# SCH_RejsaCAN_v2_5.net
KiCad netlist of a schematic drawn in EasyEDA
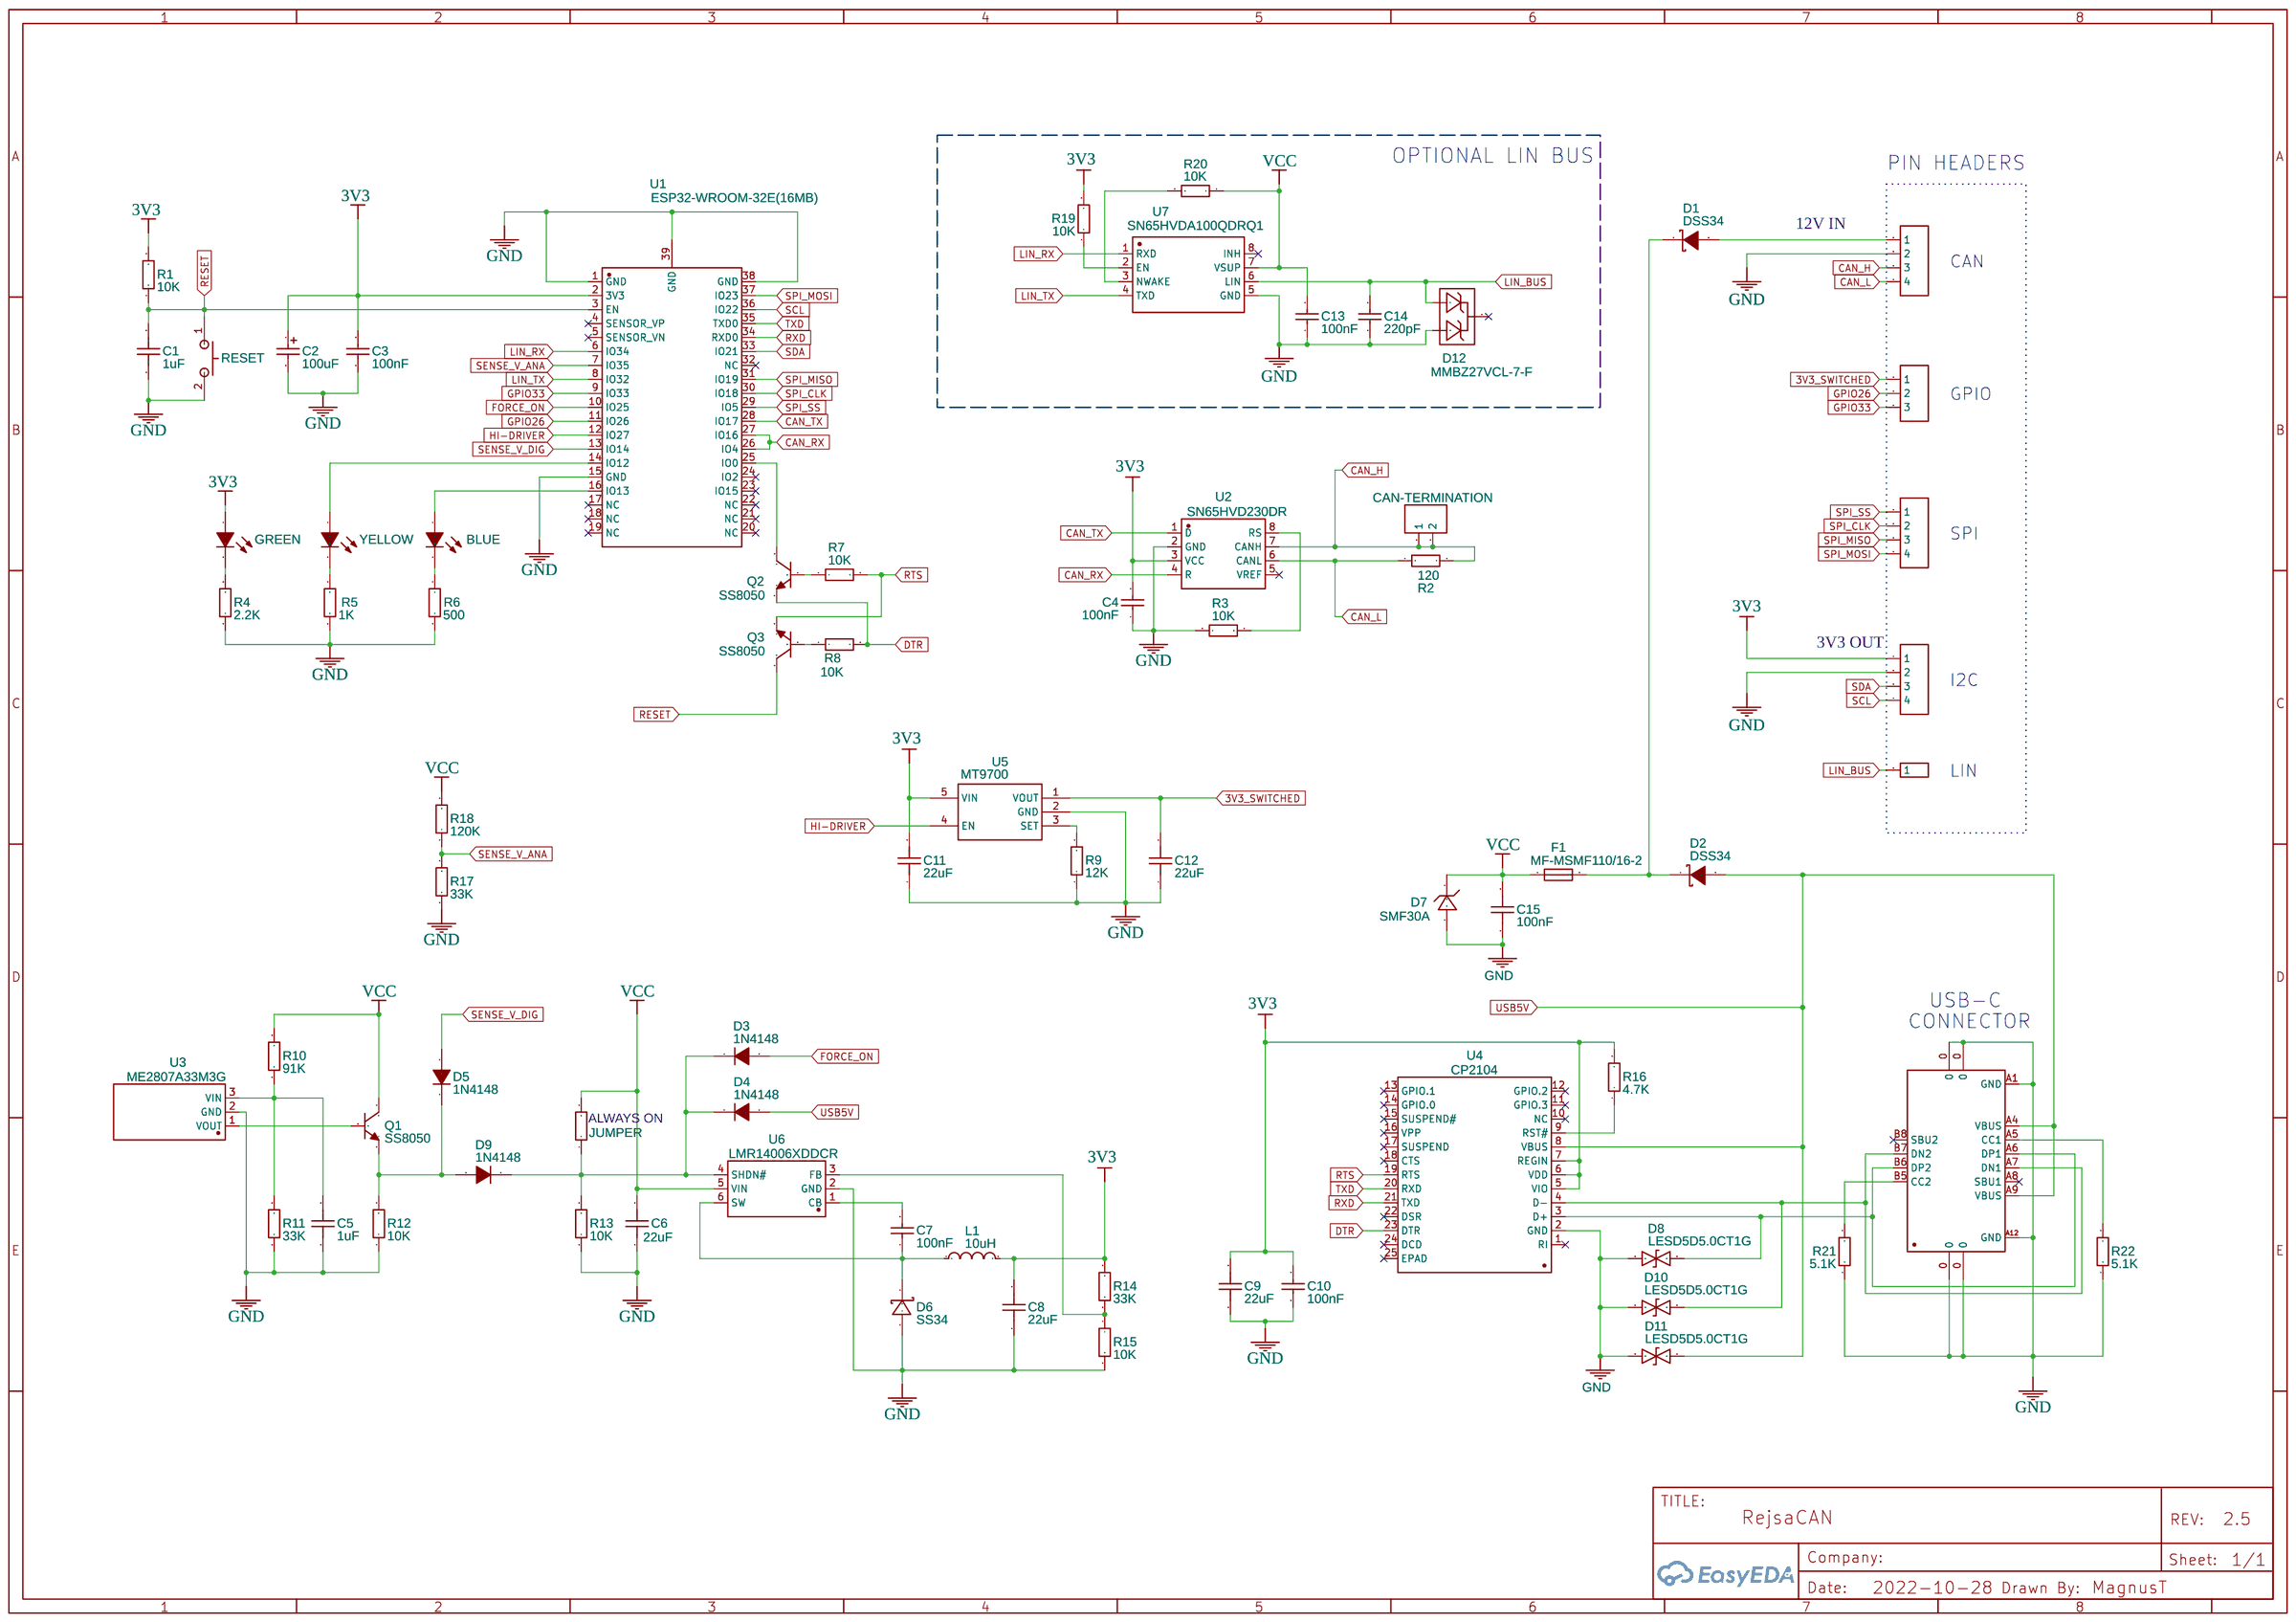
[diagram p0: schematic sheet]

(export (version "E")
  (design (tool "Eeschema 10.0.6"))
  (components
    (comp (ref "BLUE")
      (value "19-217/BHC-ZL1M2RY/3T")
      (fields (field (name "Manufacturer") "EVERLIGHT"))
      (libsource (lib "") (part "19-217/BHC-ZL1M2RY/3T"))
    )
    (comp (ref "C1")
      (value "1uF")
      (fields (field (name "Manufacturer Part") "CL05A105KA5NQNC") (field (name "Manufacturer") "SAMSUNG"))
      (libsource (lib "") (part "CL05A105KA5NQNC"))
    )
    (comp (ref "C2")
      (value "100uF")
      (fields (field (name "Manufacturer Part") "TAJB107K006RNJ") (field (name "Manufacturer") "AVX"))
      (libsource (lib "") (part "TAJB107K006RNJ"))
    )
    (comp (ref "C3")
      (value "100nF")
      (fields (field (name "Manufacturer Part") "CL05B104KO5NNNC") (field (name "Manufacturer") "SAMSUNG"))
      (libsource (lib "") (part "CL05B104KO5NNNC_1"))
    )
    (comp (ref "C4")
      (value "100nF")
      (fields (field (name "Manufacturer Part") "CL05B104KO5NNNC") (field (name "Manufacturer") "SAMSUNG"))
      (libsource (lib "") (part "CL05B104KO5NNNC"))
    )
    (comp (ref "C5")
      (value "1uF")
      (fields (field (name "Manufacturer Part") "CL05A105KA5NQNC") (field (name "Manufacturer") "SAMSUNG"))
      (libsource (lib "") (part "CL05A105KA5NQNC"))
    )
    (comp (ref "C6")
      (value "22uF")
      (fields
        (field (name "Manufacturer Part") "CL21A226MAYNNNE")
        (field (name "Manufacturer") "Samsung Electro-Mechanics")
      )
      (libsource (lib "") (part "CL21A226MAYNNNE"))
    )
    (comp (ref "C7")
      (value "100nF")
      (fields (field (name "Manufacturer Part") "CL05B104KO5NNNC") (field (name "Manufacturer") "SAMSUNG"))
      (libsource (lib "") (part "CL05B104KO5NNNC_1"))
    )
    (comp (ref "C8")
      (value "22uF")
      (fields (field (name "Manufacturer Part") "CL10A226MQ8NRNC") (field (name "Manufacturer") "SAMSUNG"))
      (libsource (lib "") (part "CL10A226MQ8NRNC"))
    )
    (comp (ref "C9")
      (value "22uF")
      (fields (field (name "Manufacturer Part") "CL10A226MQ8NRNC") (field (name "Manufacturer") "SAMSUNG"))
      (libsource (lib "") (part "CL10A226MQ8NRNC"))
    )
    (comp (ref "C10")
      (value "100nF")
      (fields (field (name "Manufacturer Part") "CL05B104KO5NNNC") (field (name "Manufacturer") "SAMSUNG"))
      (libsource (lib "") (part "CL05B104KO5NNNC_1"))
    )
    (comp (ref "C11")
      (value "22uF")
      (fields (field (name "Manufacturer Part") "CL10A226MQ8NRNC") (field (name "Manufacturer") "SAMSUNG"))
      (libsource (lib "") (part "CL10A226MQ8NRNC"))
    )
    (comp (ref "C12")
      (value "22uF")
      (fields (field (name "Manufacturer Part") "CL10A226MQ8NRNC") (field (name "Manufacturer") "SAMSUNG"))
      (libsource (lib "") (part "CL10A226MQ8NRNC"))
    )
    (comp (ref "C13")
      (value "100nF")
      (fields (field (name "Manufacturer Part") "CL05B104KO5NNNC") (field (name "Manufacturer") "SAMSUNG"))
      (libsource (lib "") (part "CL05B104KO5NNNC_1"))
    )
    (comp (ref "C14")
      (value "220pF")
      (fields (field (name "Manufacturer Part") "0402B221K500NT") (field (name "Manufacturer") "FH"))
      (libsource (lib "") (part "0402B221K500NT"))
    )
    (comp (ref "C15")
      (value "100nF")
      (fields
        (field (name "Manufacturer Part") "CL05B104KB54PNC")
        (field (name "Manufacturer") "Samsung Electro-Mechanics")
      )
      (libsource (lib "") (part "CL05B104KB54PNC"))
    )
    (comp (ref "CAN-TERMINATION") (value "HDR-M-2.54_1x2") (libsource (lib "") (part "HDR-M-2.54_1x2")))
    (comp (ref "D1")
      (value "DSS34")
      (fields (field (name "Manufacturer") "STARSEA"))
      (libsource (lib "") (part "DSS34"))
    )
    (comp (ref "D2")
      (value "DSS34")
      (fields (field (name "Manufacturer") "STARSEA"))
      (libsource (lib "") (part "DSS34"))
    )
    (comp (ref "D3")
      (value "1N4148")
      (fields (field (name "Manufacturer Part") "1N4148WS T4") (field (name "Manufacturer") "CJ"))
      (libsource (lib "") (part "1N4148WS T4"))
    )
    (comp (ref "D4")
      (value "1N4148")
      (fields (field (name "Manufacturer Part") "1N4148WS T4") (field (name "Manufacturer") "CJ"))
      (libsource (lib "") (part "1N4148WS T4"))
    )
    (comp (ref "D5")
      (value "1N4148")
      (fields (field (name "Manufacturer Part") "1N4148WS T4") (field (name "Manufacturer") "CJ"))
      (libsource (lib "") (part "1N4148WS T4_2"))
    )
    (comp (ref "D6")
      (value "SS34")
      (fields (field (name "Manufacturer") "MDD"))
      (libsource (lib "") (part "SS34_C8678"))
    )
    (comp (ref "D7")
      (value "SMF30A")
      (fields (field (name "Manufacturer") "DOWO"))
      (libsource (lib "") (part "SMF30A_C366558"))
    )
    (comp (ref "D8")
      (value "LESD5D5.0CT1G")
      (fields (field (name "Manufacturer") "Leshan Radio"))
      (libsource (lib "") (part "LESD5D5.0CT1G"))
    )
    (comp (ref "D9")
      (value "1N4148")
      (fields (field (name "Manufacturer Part") "1N4148WS T4") (field (name "Manufacturer") "CJ"))
      (libsource (lib "") (part "1N4148WS T4_1"))
    )
    (comp (ref "D10")
      (value "LESD5D5.0CT1G")
      (fields (field (name "Manufacturer") "Leshan Radio"))
      (libsource (lib "") (part "LESD5D5.0CT1G"))
    )
    (comp (ref "D11")
      (value "LESD5D5.0CT1G")
      (fields (field (name "Manufacturer") "Leshan Radio"))
      (libsource (lib "") (part "LESD5D5.0CT1G"))
    )
    (comp (ref "D12")
      (value "MMBZ27VCL-7-F")
      (fields (field (name "Manufacturer") "Diodes Incorporated"))
      (libsource (lib "") (part "MMBZ27VCL-7-F"))
    )
    (comp (ref "F1")
      (value "MF-MSMF110/16-2")
      (fields (field (name "Manufacturer") "BOURNS"))
      (libsource (lib "") (part "MF-MSMF110/16-2"))
    )
    (comp (ref "GREEN")
      (value "19-217/GHC-YR1S2/3T")
      (fields (field (name "Manufacturer") "EVERLIGHT"))
      (libsource (lib "") (part "19-217/GHC-YR1S2/3T"))
    )
    (comp (ref "J1") (value "HDR-M-2.54_1x4") (libsource (lib "") (part "HDR-M-2.54_1x4")))
    (comp (ref "J2") (value "HDR-M-2.54_1x4") (libsource (lib "") (part "HDR-M-2.54_1x4")))
    (comp (ref "J3") (value "HDR-M-2.54_1x4") (libsource (lib "") (part "HDR-M-2.54_1x4")))
    (comp (ref "J4") (value "HDR-M-2.54_1x3") (libsource (lib "") (part "HDR-M-2.54_1x3")))
    (comp (ref "J5") (value "HDR-M-2.54_1x1") (libsource (lib "") (part "HDR-M-2.54_1x1")))
    (comp (ref "JUMPER") (value "-") (libsource (lib "") (part "0402WGF3092TCE")))
    (comp (ref "L1")
      (value "10uH")
      (fields
        (field (name "Manufacturer Part") "SLP6028S100MTT")
        (field (name "Manufacturer") "Sunltech Tech")
      )
      (libsource (lib "") (part "SLP6028S100MTT"))
    )
    (comp (ref "Q1")
      (value "SS8050")
      (fields (field (name "Manufacturer") "CJ"))
      (libsource (lib "") (part "SS8050_C2150_1"))
    )
    (comp (ref "Q2")
      (value "SS8050")
      (fields (field (name "Manufacturer") "CJ"))
      (libsource (lib "") (part "SS8050_C2150_2"))
    )
    (comp (ref "Q3")
      (value "SS8050")
      (fields (field (name "Manufacturer") "CJ"))
      (libsource (lib "") (part "SS8050_C2150"))
    )
    (comp (ref "R1")
      (value "10K")
      (fields (field (name "Manufacturer Part") "0402WGF1002TCE") (field (name "Manufacturer") "UniOhm"))
      (libsource (lib "") (part "0402WGF1002TCE_1"))
    )
    (comp (ref "R2")
      (value "120")
      (fields (field (name "Manufacturer Part") "RTT061200FTP") (field (name "Manufacturer") "RALEC"))
      (libsource (lib "") (part "RTT061200FTP"))
    )
    (comp (ref "R3")
      (value "10K")
      (fields (field (name "Manufacturer Part") "0402WGF1002TCE") (field (name "Manufacturer") "UniOhm"))
      (libsource (lib "") (part "0402WGF1002TCE"))
    )
    (comp (ref "R4")
      (value "2.2K")
      (fields (field (name "Manufacturer Part") "0402WGF2201TCE") (field (name "Manufacturer") "UniOhm"))
      (libsource (lib "") (part "0402WGF2201TCE"))
    )
    (comp (ref "R5")
      (value "1K")
      (fields (field (name "Manufacturer Part") "0402WGF1001TCE") (field (name "Manufacturer") "UniOhm"))
      (libsource (lib "") (part "0402WGF1001TCE"))
    )
    (comp (ref "R6")
      (value "500")
      (fields (field (name "Manufacturer Part") "0402WGF4700TCE") (field (name "Manufacturer") "UniOhm"))
      (libsource (lib "") (part "0402WGF1001TCE"))
    )
    (comp (ref "R7")
      (value "10K")
      (fields (field (name "Manufacturer Part") "0402WGF1002TCE") (field (name "Manufacturer") "UniOhm"))
      (libsource (lib "") (part "0402WGF1002TCE"))
    )
    (comp (ref "R8")
      (value "10K")
      (fields (field (name "Manufacturer Part") "0402WGF1002TCE") (field (name "Manufacturer") "UniOhm"))
      (libsource (lib "") (part "0402WGF1002TCE"))
    )
    (comp (ref "R9")
      (value "12K")
      (fields (field (name "Manufacturer Part") "0402WGF1202TCE") (field (name "Manufacturer") "UniOhm"))
      (libsource (lib "") (part "0402WGF1202TCE"))
    )
    (comp (ref "R10")
      (value "91K")
      (fields (field (name "Manufacturer Part") "0402WGF9102TCE") (field (name "Manufacturer") "UniOhm"))
      (libsource (lib "") (part "0402WGF9102TCE"))
    )
    (comp (ref "R11")
      (value "33K")
      (fields (field (name "Manufacturer Part") "0402WGF3302TCE") (field (name "Manufacturer") "UniOhm"))
      (libsource (lib "") (part "0402WGF3302TCE"))
    )
    (comp (ref "R12")
      (value "10K")
      (fields (field (name "Manufacturer Part") "0402WGF1002TCE") (field (name "Manufacturer") "UniOhm"))
      (libsource (lib "") (part "0402WGF1002TCE_1"))
    )
    (comp (ref "R13")
      (value "10K")
      (fields (field (name "Manufacturer Part") "0402WGF1002TCE") (field (name "Manufacturer") "UniOhm"))
      (libsource (lib "") (part "0402WGF1002TCE_1"))
    )
    (comp (ref "R14")
      (value "33K")
      (fields (field (name "Manufacturer Part") "0402WGF3302TCE") (field (name "Manufacturer") "UniOhm"))
      (libsource (lib "") (part "0402WGF3302TCE"))
    )
    (comp (ref "R15")
      (value "10K")
      (fields (field (name "Manufacturer Part") "0402WGF1002TCE") (field (name "Manufacturer") "UniOhm"))
      (libsource (lib "") (part "0402WGF1002TCE_3"))
    )
    (comp (ref "R16")
      (value "4.7K")
      (fields (field (name "Manufacturer Part") "0402WGF4701TCE") (field (name "Manufacturer") "UniOhm"))
      (libsource (lib "") (part "0402WGF4701TCE"))
    )
    (comp (ref "R17")
      (value "33K")
      (fields (field (name "Manufacturer Part") "0402WGF3302TCE") (field (name "Manufacturer") "UniOhm"))
      (libsource (lib "") (part "0402WGF3302TCE"))
    )
    (comp (ref "R18")
      (value "120K")
      (fields (field (name "Manufacturer Part") "0402WGF1203TCE") (field (name "Manufacturer") "UniOhm"))
      (libsource (lib "") (part "0402WGF1203TCE"))
    )
    (comp (ref "R19")
      (value "10K")
      (fields (field (name "Manufacturer Part") "0402WGF1002TCE") (field (name "Manufacturer") "UniOhm"))
      (libsource (lib "") (part "0402WGF1002TCE_1"))
    )
    (comp (ref "R20")
      (value "10K")
      (fields (field (name "Manufacturer Part") "0402WGF1002TCE") (field (name "Manufacturer") "UniOhm"))
      (libsource (lib "") (part "0402WGF1002TCE_2"))
    )
    (comp (ref "R21")
      (value "5.1K")
      (fields (field (name "Manufacturer Part") "0402WGF5101TCE") (field (name "Manufacturer") "UniOhm"))
      (libsource (lib "") (part "0402WGF5101TCE"))
    )
    (comp (ref "R22")
      (value "5.1K")
      (fields (field (name "Manufacturer Part") "0402WGF5101TCE") (field (name "Manufacturer") "UniOhm"))
      (libsource (lib "") (part "0402WGF5101TCE"))
    )
    (comp (ref "RESET")
      (value "GT-TC029B-H025-L1N")
      (fields (field (name "Manufacturer") "G-Switch"))
      (libsource (lib "") (part "GT-TC029B-H025-L1N"))
    )
    (comp (ref "U1")
      (value "ESP32-WROOM-32E(16MB)")
      (fields (field (name "Manufacturer") "Espressif Systems"))
      (libsource (lib "") (part "ESP32-WROOM-32E(16MB)"))
    )
    (comp (ref "U2")
      (value "SN65HVD230DR")
      (fields (field (name "Manufacturer") "TI"))
      (libsource (lib "") (part "SN65HVD230DR"))
    )
    (comp (ref "U3")
      (value "ME2807A33M3G")
      (fields (field (name "Manufacturer") "Nanjing Micro One Elec"))
      (libsource (lib "") (part "ME2807A33M3G"))
    )
    (comp (ref "U4")
      (value "CP2104")
      (fields (field (name "Manufacturer Part") "CP2104-F03-GM") (field (name "Manufacturer") "SILICON LABS"))
      (libsource (lib "") (part "CP2104-F03-GM"))
    )
    (comp (ref "U5")
      (value "MT9700")
      (fields (field (name "Manufacturer") "AEROSEMI"))
      (libsource (lib "") (part "MT9700"))
    )
    (comp (ref "U6")
      (value "LMR14006XDDCR")
      (fields (field (name "Manufacturer") "Texas Instruments"))
      (libsource (lib "") (part "LMR14006XDDCR"))
    )
    (comp (ref "U7")
      (value "SN65HVDA100QDRQ1")
      (fields (field (name "Manufacturer") "TI"))
      (libsource (lib "") (part "SN65HVDA100QDRQ1"))
    )
    (comp (ref "USB-C")
      (value "USB3.1C16PFSMT")
      (fields (field (name "Manufacturer") "LCSC"))
      (libsource (lib "") (part "USB3.1C16PFSMT"))
    )
    (comp (ref "YELLOW")
      (value "19-213/Y2C-CQ2R2L/3T(CY)")
      (fields (field (name "Manufacturer") "EVERLIGHT"))
      (libsource (lib "") (part "19-213/Y2C-CQ2R2L/3T(CY)"))
    )
  )
  (nets
    (net (code "1") (name "3V3") (class "Default")
      (node (ref "C10") (pin "2") (pinfunction "2_2") (pintype "input"))
      (node (ref "C11") (pin "2") (pinfunction "2_2") (pintype "unspecified"))
      (node (ref "C2") (pin "1") (pinfunction "1_1") (pintype "input"))
      (node (ref "C3") (pin "2") (pinfunction "2_2") (pintype "input"))
      (node (ref "C4") (pin "2") (pinfunction "2_2") (pintype "input"))
      (node (ref "C8") (pin "2") (pinfunction "2_2") (pintype "unspecified"))
      (node (ref "C9") (pin "2") (pinfunction "2_2") (pintype "unspecified"))
      (node (ref "GREEN") (pin "1") (pinfunction "A_1") (pintype "input"))
      (node (ref "J2") (pin "1") (pinfunction "1_1") (pintype "unspecified"))
      (node (ref "L1") (pin "2") (pinfunction "2_2") (pintype "unspecified"))
      (node (ref "R1") (pin "2") (pinfunction "2_2") (pintype "input"))
      (node (ref "R14") (pin "2") (pinfunction "2_2") (pintype "input"))
      (node (ref "R16") (pin "2") (pinfunction "2_2") (pintype "input"))
      (node (ref "R19") (pin "2") (pinfunction "2_2") (pintype "input"))
      (node (ref "U1") (pin "2") (pinfunction "3V3_2") (pintype "unspecified"))
      (node (ref "U2") (pin "3") (pinfunction "VCC_3") (pintype "unspecified"))
      (node (ref "U4") (pin "5") (pinfunction "VIO_5") (pintype "unspecified"))
      (node (ref "U4") (pin "6") (pinfunction "VDD_6") (pintype "unspecified"))
      (node (ref "U4") (pin "7") (pinfunction "REGIN_7") (pintype "unspecified"))
      (node (ref "U5") (pin "5") (pinfunction "VIN_5") (pintype "unspecified"))
    )
    (net (code "2") (name "3V3_SWITCHED") (class "Default")
      (node (ref "C12") (pin "2") (pinfunction "2_2") (pintype "unspecified"))
      (node (ref "J4") (pin "1") (pinfunction "1_1") (pintype "input"))
      (node (ref "U5") (pin "1") (pinfunction "VOUT_1") (pintype "unspecified"))
    )
    (net (code "3") (name "CAN_H") (class "Default")
      (node (ref "CAN-TERMINATION") (pin "1") (pinfunction "1_1") (pintype "unspecified"))
      (node (ref "CAN-TERMINATION") (pin "2") (pinfunction "2_2") (pintype "unspecified"))
      (node (ref "J1") (pin "3") (pinfunction "3_3") (pintype "unspecified"))
      (node (ref "R2") (pin "2") (pinfunction "2_2") (pintype "unspecified"))
      (node (ref "U2") (pin "7") (pinfunction "CANH_7") (pintype "unspecified"))
    )
    (net (code "4") (name "CAN_L") (class "Default")
      (node (ref "J1") (pin "4") (pinfunction "4_4") (pintype "unspecified"))
      (node (ref "R2") (pin "1") (pinfunction "1_1") (pintype "unspecified"))
      (node (ref "U2") (pin "6") (pinfunction "CANL_6") (pintype "unspecified"))
    )
    (net (code "5") (name "CAN_RX") (class "Default")
      (node (ref "U1") (pin "26") (pinfunction "IO4_26") (pintype "unspecified"))
      (node (ref "U1") (pin "27") (pinfunction "IO16_27") (pintype "unspecified"))
      (node (ref "U2") (pin "4") (pinfunction "R_4") (pintype "unspecified"))
    )
    (net (code "6") (name "CAN_TX") (class "Default")
      (node (ref "U1") (pin "28") (pinfunction "IO17_28") (pintype "unspecified"))
      (node (ref "U2") (pin "1") (pinfunction "D_1") (pintype "unspecified"))
    )
    (net (code "7") (name "DTR") (class "Default")
      (node (ref "Q2") (pin "2") (pinfunction "E_2") (pintype "unspecified"))
      (node (ref "R8") (pin "2") (pinfunction "2_2") (pintype "input"))
      (node (ref "U4") (pin "23") (pinfunction "DTR_23") (pintype "unspecified"))
    )
    (net (code "8") (name "FORCE_ON") (class "Default")
      (node (ref "D3") (pin "2") (pinfunction "A_2") (pintype "unspecified"))
      (node (ref "U1") (pin "10") (pinfunction "IO25_10") (pintype "unspecified"))
    )
    (net (code "9") (name "GND") (class "Default")
      (node (ref "C1") (pin "1") (pinfunction "1_1") (pintype "unspecified"))
      (node (ref "C10") (pin "1") (pinfunction "1_1") (pintype "input"))
      (node (ref "C11") (pin "1") (pinfunction "1_1") (pintype "unspecified"))
      (node (ref "C12") (pin "1") (pinfunction "1_1") (pintype "unspecified"))
      (node (ref "C13") (pin "1") (pinfunction "1_1") (pintype "input"))
      (node (ref "C14") (pin "1") (pinfunction "1_1") (pintype "input"))
      (node (ref "C15") (pin "1") (pinfunction "1_1") (pintype "unspecified"))
      (node (ref "C2") (pin "2") (pinfunction "2_2") (pintype "input"))
      (node (ref "C3") (pin "1") (pinfunction "1_1") (pintype "input"))
      (node (ref "C4") (pin "1") (pinfunction "1_1") (pintype "input"))
      (node (ref "C5") (pin "1") (pinfunction "1_1") (pintype "unspecified"))
      (node (ref "C6") (pin "1") (pinfunction "1_1") (pintype "unspecified"))
      (node (ref "C8") (pin "1") (pinfunction "1_1") (pintype "unspecified"))
      (node (ref "C9") (pin "1") (pinfunction "1_1") (pintype "unspecified"))
      (node (ref "D10") (pin "2") (pinfunction "2_2") (pintype "unspecified"))
      (node (ref "D11") (pin "2") (pinfunction "2_2") (pintype "unspecified"))
      (node (ref "D12") (pin "2") (pinfunction "2_2") (pintype "unspecified"))
      (node (ref "D6") (pin "2") (pinfunction "A_2") (pintype "unspecified"))
      (node (ref "D7") (pin "2") (pinfunction "2_2") (pintype "unspecified"))
      (node (ref "D8") (pin "2") (pinfunction "2_2") (pintype "unspecified"))
      (node (ref "J1") (pin "2") (pinfunction "2_2") (pintype "unspecified"))
      (node (ref "J2") (pin "2") (pinfunction "2_2") (pintype "unspecified"))
      (node (ref "R11") (pin "1") (pinfunction "1_1") (pintype "input"))
      (node (ref "R12") (pin "1") (pinfunction "1_1") (pintype "input"))
      (node (ref "R13") (pin "1") (pinfunction "1_1") (pintype "input"))
      (node (ref "R15") (pin "2") (pinfunction "2_2") (pintype "input"))
      (node (ref "R17") (pin "1") (pinfunction "1_1") (pintype "input"))
      (node (ref "R21") (pin "1") (pinfunction "1_1") (pintype "input"))
      (node (ref "R22") (pin "1") (pinfunction "1_1") (pintype "input"))
      (node (ref "R3") (pin "1") (pinfunction "1_1") (pintype "input"))
      (node (ref "R4") (pin "1") (pinfunction "1_1") (pintype "input"))
      (node (ref "R5") (pin "2") (pinfunction "2_2") (pintype "input"))
      (node (ref "R6") (pin "2") (pinfunction "2_2") (pintype "input"))
      (node (ref "R9") (pin "1") (pinfunction "1_1") (pintype "input"))
      (node (ref "RESET") (pin "2") (pinfunction "2_2") (pintype "unspecified"))
      (node (ref "U1") (pin "1") (pinfunction "GND_1") (pintype "unspecified"))
      (node (ref "U1") (pin "15") (pinfunction "GND_15") (pintype "unspecified"))
      (node (ref "U1") (pin "38") (pinfunction "GND_38") (pintype "unspecified"))
      (node (ref "U1") (pin "39") (pinfunction "GND_39") (pintype "unspecified"))
      (node (ref "U2") (pin "2") (pinfunction "GND_2") (pintype "unspecified"))
      (node (ref "U3") (pin "2") (pinfunction "GND_2") (pintype "unspecified"))
      (node (ref "U4") (pin "2") (pinfunction "GND_2") (pintype "unspecified"))
      (node (ref "U5") (pin "2") (pinfunction "GND_2") (pintype "unspecified"))
      (node (ref "U6") (pin "2") (pinfunction "GND_2") (pintype "unspecified"))
      (node (ref "U7") (pin "5") (pinfunction "GND_5") (pintype "unspecified"))
      (node (ref "USB-C") (pin "0") (pinfunction "0_0") (pintype "unspecified"))
      (node (ref "USB-C") (pin "A1") (pinfunction "GND_A1") (pintype "unspecified"))
      (node (ref "USB-C") (pin "A12") (pinfunction "GND_A12") (pintype "unspecified"))
    )
    (net (code "10") (name "GPIO26") (class "Default")
      (node (ref "J4") (pin "2") (pinfunction "2_2") (pintype "input"))
      (node (ref "U1") (pin "11") (pinfunction "IO26_11") (pintype "unspecified"))
    )
    (net (code "11") (name "GPIO33") (class "Default")
      (node (ref "J4") (pin "3") (pinfunction "3_3") (pintype "input"))
      (node (ref "U1") (pin "9") (pinfunction "IO33_9") (pintype "unspecified"))
    )
    (net (code "12") (name "HI-DRIVER") (class "Default")
      (node (ref "U1") (pin "12") (pinfunction "IO27_12") (pintype "unspecified"))
      (node (ref "U5") (pin "4") (pinfunction "EN_4") (pintype "unspecified"))
    )
    (net (code "13") (name "LIN_BUS") (class "Default")
      (node (ref "C14") (pin "2") (pinfunction "2_2") (pintype "input"))
      (node (ref "D12") (pin "1") (pinfunction "1_1") (pintype "unspecified"))
      (node (ref "J5") (pin "1") (pinfunction "1_1") (pintype "input"))
      (node (ref "U7") (pin "6") (pinfunction "LIN_6") (pintype "unspecified"))
    )
    (net (code "14") (name "LIN_RX") (class "Default")
      (node (ref "U1") (pin "6") (pinfunction "IO34_6") (pintype "unspecified"))
      (node (ref "U7") (pin "1") (pinfunction "RXD_1") (pintype "unspecified"))
    )
    (net (code "15") (name "LIN_TX") (class "Default")
      (node (ref "U1") (pin "8") (pinfunction "IO32_8") (pintype "unspecified"))
      (node (ref "U7") (pin "4") (pinfunction "TXD_4") (pintype "unspecified"))
    )
    (net (code "16") (name "Net-(BLUE-A)") (class "Default")
      (node (ref "BLUE") (pin "1") (pinfunction "A_1") (pintype "input"))
      (node (ref "U1") (pin "16") (pinfunction "IO13_16") (pintype "unspecified"))
    )
    (net (code "17") (name "Net-(BLUE-C)") (class "Default")
      (node (ref "BLUE") (pin "2") (pinfunction "C_2") (pintype "input"))
      (node (ref "R6") (pin "1") (pinfunction "1_1") (pintype "input"))
    )
    (net (code "18") (name "Net-(D1-A)") (class "Default")
      (node (ref "D1") (pin "2") (pinfunction "A_2") (pintype "unspecified"))
      (node (ref "J1") (pin "1") (pinfunction "1_1") (pintype "unspecified"))
    )
    (net (code "19") (name "Net-(D1-K)") (class "Default")
      (node (ref "D1") (pin "1") (pinfunction "K_1") (pintype "unspecified"))
      (node (ref "D2") (pin "1") (pinfunction "K_1") (pintype "unspecified"))
      (node (ref "F1") (pin "2") (pinfunction "2_2") (pintype "unspecified"))
    )
    (net (code "20") (name "Net-(D3-K)") (class "Default")
      (node (ref "D3") (pin "1") (pinfunction "K_1") (pintype "unspecified"))
      (node (ref "D4") (pin "1") (pinfunction "K_1") (pintype "unspecified"))
      (node (ref "D9") (pin "1") (pinfunction "K_1") (pintype "unspecified"))
      (node (ref "JUMPER") (pin "1") (pinfunction "1_1") (pintype "unspecified"))
      (node (ref "R13") (pin "2") (pinfunction "2_2") (pintype "input"))
      (node (ref "U6") (pin "4") (pinfunction "SHDN#_4") (pintype "unspecified"))
    )
    (net (code "21") (name "Net-(D5-K)") (class "Default")
      (node (ref "D5") (pin "1") (pinfunction "K_1") (pintype "unspecified"))
      (node (ref "D9") (pin "2") (pinfunction "A_2") (pintype "unspecified"))
      (node (ref "Q1") (pin "2") (pinfunction "E_2") (pintype "unspecified"))
      (node (ref "R12") (pin "2") (pinfunction "2_2") (pintype "input"))
    )
    (net (code "22") (name "Net-(D6-K)") (class "Default")
      (node (ref "C7") (pin "1") (pinfunction "1_1") (pintype "input"))
      (node (ref "D6") (pin "1") (pinfunction "K_1") (pintype "unspecified"))
      (node (ref "L1") (pin "1") (pinfunction "1_1") (pintype "unspecified"))
      (node (ref "U6") (pin "6") (pinfunction "SW_6") (pintype "unspecified"))
    )
    (net (code "23") (name "Net-(GREEN-C)") (class "Default")
      (node (ref "GREEN") (pin "2") (pinfunction "C_2") (pintype "input"))
      (node (ref "R4") (pin "2") (pinfunction "2_2") (pintype "input"))
    )
    (net (code "24") (name "Net-(Q1-B)") (class "Default")
      (node (ref "Q1") (pin "1") (pinfunction "B_1") (pintype "unspecified"))
      (node (ref "U3") (pin "1") (pinfunction "VOUT_1") (pintype "unspecified"))
    )
    (net (code "25") (name "Net-(Q2-B)") (class "Default")
      (node (ref "Q2") (pin "1") (pinfunction "B_1") (pintype "unspecified"))
      (node (ref "R7") (pin "1") (pinfunction "1_1") (pintype "input"))
    )
    (net (code "26") (name "Net-(Q2-C)") (class "Default")
      (node (ref "Q2") (pin "3") (pinfunction "C_3") (pintype "unspecified"))
      (node (ref "U1") (pin "25") (pinfunction "IO0_25") (pintype "unspecified"))
    )
    (net (code "27") (name "Net-(Q3-B)") (class "Default")
      (node (ref "Q3") (pin "1") (pinfunction "B_1") (pintype "unspecified"))
      (node (ref "R8") (pin "1") (pinfunction "1_1") (pintype "input"))
    )
    (net (code "28") (name "Net-(U1-IO12)") (class "Default")
      (node (ref "U1") (pin "14") (pinfunction "IO12_14") (pintype "unspecified"))
      (node (ref "YELLOW") (pin "1") (pinfunction "A_1") (pintype "input"))
    )
    (net (code "29") (name "Net-(U2-RS)") (class "Default")
      (node (ref "R3") (pin "2") (pinfunction "2_2") (pintype "input"))
      (node (ref "U2") (pin "8") (pinfunction "RS_8") (pintype "unspecified"))
    )
    (net (code "30") (name "Net-(U3-VIN)") (class "Default")
      (node (ref "C5") (pin "2") (pinfunction "2_2") (pintype "unspecified"))
      (node (ref "R10") (pin "1") (pinfunction "1_1") (pintype "input"))
      (node (ref "R11") (pin "2") (pinfunction "2_2") (pintype "input"))
      (node (ref "U3") (pin "3") (pinfunction "VIN_3") (pintype "unspecified"))
    )
    (net (code "31") (name "Net-(U4-D+)") (class "Default")
      (node (ref "D8") (pin "1") (pinfunction "1_1") (pintype "unspecified"))
      (node (ref "U4") (pin "3") (pinfunction "D+_3") (pintype "unspecified"))
      (node (ref "USB-C") (pin "A6") (pinfunction "DP1_A6") (pintype "unspecified"))
      (node (ref "USB-C") (pin "B6") (pinfunction "DP2_B6") (pintype "unspecified"))
    )
    (net (code "32") (name "Net-(U4-D-)") (class "Default")
      (node (ref "D10") (pin "1") (pinfunction "1_1") (pintype "unspecified"))
      (node (ref "U4") (pin "4") (pinfunction "D-_4") (pintype "unspecified"))
      (node (ref "USB-C") (pin "A7") (pinfunction "DN1_A7") (pintype "unspecified"))
      (node (ref "USB-C") (pin "B7") (pinfunction "DN2_B7") (pintype "unspecified"))
    )
    (net (code "33") (name "Net-(U4-RST#)") (class "Default")
      (node (ref "R16") (pin "1") (pinfunction "1_1") (pintype "input"))
      (node (ref "U4") (pin "9") (pinfunction "RST#_9") (pintype "unspecified"))
    )
    (net (code "34") (name "Net-(U5-SET)") (class "Default")
      (node (ref "R9") (pin "2") (pinfunction "2_2") (pintype "input"))
      (node (ref "U5") (pin "3") (pinfunction "SET_3") (pintype "unspecified"))
    )
    (net (code "35") (name "Net-(U6-CB)") (class "Default")
      (node (ref "C7") (pin "2") (pinfunction "2_2") (pintype "input"))
      (node (ref "U6") (pin "1") (pinfunction "CB_1") (pintype "unspecified"))
    )
    (net (code "36") (name "Net-(U6-FB)") (class "Default")
      (node (ref "R14") (pin "1") (pinfunction "1_1") (pintype "input"))
      (node (ref "R15") (pin "1") (pinfunction "1_1") (pintype "input"))
      (node (ref "U6") (pin "3") (pinfunction "FB_3") (pintype "unspecified"))
    )
    (net (code "37") (name "Net-(U7-EN)") (class "Default")
      (node (ref "R19") (pin "1") (pinfunction "1_1") (pintype "input"))
      (node (ref "U7") (pin "2") (pinfunction "EN_2") (pintype "unspecified"))
    )
    (net (code "38") (name "Net-(U7-NWAKE)") (class "Default")
      (node (ref "R20") (pin "2") (pinfunction "2_2") (pintype "input"))
      (node (ref "U7") (pin "3") (pinfunction "NWAKE_3") (pintype "unspecified"))
    )
    (net (code "39") (name "Net-(USB-C-CC1)") (class "Default")
      (node (ref "R22") (pin "2") (pinfunction "2_2") (pintype "input"))
      (node (ref "USB-C") (pin "A5") (pinfunction "CC1_A5") (pintype "unspecified"))
    )
    (net (code "40") (name "Net-(USB-C-CC2)") (class "Default")
      (node (ref "R21") (pin "2") (pinfunction "2_2") (pintype "input"))
      (node (ref "USB-C") (pin "B5") (pinfunction "CC2_B5") (pintype "unspecified"))
    )
    (net (code "41") (name "Net-(YELLOW-C)") (class "Default")
      (node (ref "R5") (pin "1") (pinfunction "1_1") (pintype "input"))
      (node (ref "YELLOW") (pin "2") (pinfunction "C_2") (pintype "input"))
    )
    (net (code "42") (name "RESET") (class "Default")
      (node (ref "C1") (pin "2") (pinfunction "2_2") (pintype "unspecified"))
      (node (ref "Q3") (pin "3") (pinfunction "C_3") (pintype "unspecified"))
      (node (ref "R1") (pin "1") (pinfunction "1_1") (pintype "input"))
      (node (ref "RESET") (pin "1") (pinfunction "1_1") (pintype "unspecified"))
      (node (ref "U1") (pin "3") (pinfunction "EN_3") (pintype "unspecified"))
    )
    (net (code "43") (name "RTS") (class "Default")
      (node (ref "Q3") (pin "2") (pinfunction "E_2") (pintype "unspecified"))
      (node (ref "R7") (pin "2") (pinfunction "2_2") (pintype "input"))
      (node (ref "U4") (pin "19") (pinfunction "RTS_19") (pintype "unspecified"))
    )
    (net (code "44") (name "RXD") (class "Default")
      (node (ref "U1") (pin "34") (pinfunction "RXD0_34") (pintype "unspecified"))
      (node (ref "U4") (pin "21") (pinfunction "TXD_21") (pintype "unspecified"))
    )
    (net (code "45") (name "SCL") (class "Default")
      (node (ref "J2") (pin "4") (pinfunction "4_4") (pintype "unspecified"))
      (node (ref "U1") (pin "36") (pinfunction "IO22_36") (pintype "unspecified"))
    )
    (net (code "46") (name "SDA") (class "Default")
      (node (ref "J2") (pin "3") (pinfunction "3_3") (pintype "unspecified"))
      (node (ref "U1") (pin "33") (pinfunction "IO21_33") (pintype "unspecified"))
    )
    (net (code "47") (name "SENSE_V_ANA") (class "Default")
      (node (ref "R17") (pin "2") (pinfunction "2_2") (pintype "input"))
      (node (ref "R18") (pin "1") (pinfunction "1_1") (pintype "input"))
      (node (ref "U1") (pin "7") (pinfunction "IO35_7") (pintype "unspecified"))
    )
    (net (code "48") (name "SENSE_V_DIG") (class "Default")
      (node (ref "D5") (pin "2") (pinfunction "A_2") (pintype "unspecified"))
      (node (ref "U1") (pin "13") (pinfunction "IO14_13") (pintype "unspecified"))
    )
    (net (code "49") (name "SPI_CLK") (class "Default")
      (node (ref "J3") (pin "2") (pinfunction "2_2") (pintype "unspecified"))
      (node (ref "U1") (pin "30") (pinfunction "IO18_30") (pintype "unspecified"))
    )
    (net (code "50") (name "SPI_MISO") (class "Default")
      (node (ref "J3") (pin "3") (pinfunction "3_3") (pintype "unspecified"))
      (node (ref "U1") (pin "31") (pinfunction "IO19_31") (pintype "unspecified"))
    )
    (net (code "51") (name "SPI_MOSI") (class "Default")
      (node (ref "J3") (pin "4") (pinfunction "4_4") (pintype "unspecified"))
      (node (ref "U1") (pin "37") (pinfunction "IO23_37") (pintype "unspecified"))
    )
    (net (code "52") (name "SPI_SS") (class "Default")
      (node (ref "J3") (pin "1") (pinfunction "1_1") (pintype "unspecified"))
      (node (ref "U1") (pin "29") (pinfunction "IO5_29") (pintype "unspecified"))
    )
    (net (code "53") (name "TXD") (class "Default")
      (node (ref "U1") (pin "35") (pinfunction "TXD0_35") (pintype "unspecified"))
      (node (ref "U4") (pin "20") (pinfunction "RXD_20") (pintype "unspecified"))
    )
    (net (code "54") (name "USB5V") (class "Default")
      (node (ref "D11") (pin "1") (pinfunction "1_1") (pintype "unspecified"))
      (node (ref "D2") (pin "2") (pinfunction "A_2") (pintype "unspecified"))
      (node (ref "D4") (pin "2") (pinfunction "A_2") (pintype "unspecified"))
      (node (ref "U4") (pin "8") (pinfunction "VBUS_8") (pintype "unspecified"))
      (node (ref "USB-C") (pin "A4") (pinfunction "VBUS_A4") (pintype "unspecified"))
      (node (ref "USB-C") (pin "A9") (pinfunction "VBUS_A9") (pintype "unspecified"))
    )
    (net (code "55") (name "VCC") (class "Default")
      (node (ref "C13") (pin "2") (pinfunction "2_2") (pintype "input"))
      (node (ref "C15") (pin "2") (pinfunction "2_2") (pintype "unspecified"))
      (node (ref "C6") (pin "2") (pinfunction "2_2") (pintype "unspecified"))
      (node (ref "D7") (pin "1") (pinfunction "1_1") (pintype "unspecified"))
      (node (ref "F1") (pin "1") (pinfunction "1_1") (pintype "unspecified"))
      (node (ref "JUMPER") (pin "2") (pinfunction "2_2") (pintype "unspecified"))
      (node (ref "Q1") (pin "3") (pinfunction "C_3") (pintype "unspecified"))
      (node (ref "R10") (pin "2") (pinfunction "2_2") (pintype "input"))
      (node (ref "R18") (pin "2") (pinfunction "2_2") (pintype "input"))
      (node (ref "R20") (pin "1") (pinfunction "1_1") (pintype "input"))
      (node (ref "U6") (pin "5") (pinfunction "VIN_5") (pintype "unspecified"))
      (node (ref "U7") (pin "7") (pinfunction "VSUP_7") (pintype "unspecified"))
    )
    (net (code "56") (name "unconnected-(D12-Pad3)") (class "Default")
      (node (ref "D12") (pin "3") (pinfunction "3_3") (pintype "unspecified+no_connect"))
    )
    (net (code "57") (name "unconnected-(U1-IO2-Pad24)") (class "Default")
      (node (ref "U1") (pin "24") (pinfunction "IO2_24") (pintype "unspecified+no_connect"))
    )
    (net (code "58") (name "unconnected-(U1-IO15-Pad23)") (class "Default")
      (node (ref "U1") (pin "23") (pinfunction "IO15_23") (pintype "unspecified+no_connect"))
    )
    (net (code "59") (name "unconnected-(U1-NC-Pad17)") (class "Default")
      (node (ref "U1") (pin "17") (pinfunction "NC_17") (pintype "unspecified+no_connect"))
    )
    (net (code "60") (name "unconnected-(U1-NC-Pad18)") (class "Default")
      (node (ref "U1") (pin "18") (pinfunction "NC_18") (pintype "unspecified+no_connect"))
    )
    (net (code "61") (name "unconnected-(U1-NC-Pad19)") (class "Default")
      (node (ref "U1") (pin "19") (pinfunction "NC_19") (pintype "unspecified+no_connect"))
    )
    (net (code "62") (name "unconnected-(U1-NC-Pad20)") (class "Default")
      (node (ref "U1") (pin "20") (pinfunction "NC_20") (pintype "unspecified+no_connect"))
    )
    (net (code "63") (name "unconnected-(U1-NC-Pad21)") (class "Default")
      (node (ref "U1") (pin "21") (pinfunction "NC_21") (pintype "unspecified+no_connect"))
    )
    (net (code "64") (name "unconnected-(U1-NC-Pad22)") (class "Default")
      (node (ref "U1") (pin "22") (pinfunction "NC_22") (pintype "unspecified+no_connect"))
    )
    (net (code "65") (name "unconnected-(U1-NC-Pad32)") (class "Default")
      (node (ref "U1") (pin "32") (pinfunction "NC_32") (pintype "unspecified+no_connect"))
    )
    (net (code "66") (name "unconnected-(U1-SENSOR_VN-Pad5)") (class "Default")
      (node (ref "U1") (pin "5") (pinfunction "SENSOR_VN_5") (pintype "unspecified+no_connect"))
    )
    (net (code "67") (name "unconnected-(U1-SENSOR_VP-Pad4)") (class "Default")
      (node (ref "U1") (pin "4") (pinfunction "SENSOR_VP_4") (pintype "unspecified+no_connect"))
    )
    (net (code "68") (name "unconnected-(U2-VREF-Pad5)") (class "Default")
      (node (ref "U2") (pin "5") (pinfunction "VREF_5") (pintype "unspecified+no_connect"))
    )
    (net (code "69") (name "unconnected-(U4-CTS-Pad18)") (class "Default")
      (node (ref "U4") (pin "18") (pinfunction "CTS_18") (pintype "unspecified+no_connect"))
    )
    (net (code "70") (name "unconnected-(U4-DCD-Pad24)") (class "Default")
      (node (ref "U4") (pin "24") (pinfunction "DCD_24") (pintype "unspecified+no_connect"))
    )
    (net (code "71") (name "unconnected-(U4-DSR-Pad22)") (class "Default")
      (node (ref "U4") (pin "22") (pinfunction "DSR_22") (pintype "unspecified+no_connect"))
    )
    (net (code "72") (name "unconnected-(U4-EPAD-Pad25)") (class "Default")
      (node (ref "U4") (pin "25") (pinfunction "EPAD_25") (pintype "unspecified+no_connect"))
    )
    (net (code "73") (name "unconnected-(U4-GPIO.0-Pad14)") (class "Default")
      (node (ref "U4") (pin "14") (pinfunction "GPIO.0_14") (pintype "unspecified+no_connect"))
    )
    (net (code "74") (name "unconnected-(U4-GPIO.1-Pad13)") (class "Default")
      (node (ref "U4") (pin "13") (pinfunction "GPIO.1_13") (pintype "unspecified+no_connect"))
    )
    (net (code "75") (name "unconnected-(U4-GPIO.2-Pad12)") (class "Default")
      (node (ref "U4") (pin "12") (pinfunction "GPIO.2_12") (pintype "unspecified+no_connect"))
    )
    (net (code "76") (name "unconnected-(U4-GPIO.3-Pad11)") (class "Default")
      (node (ref "U4") (pin "11") (pinfunction "GPIO.3_11") (pintype "unspecified+no_connect"))
    )
    (net (code "77") (name "unconnected-(U4-NC-Pad10)") (class "Default")
      (node (ref "U4") (pin "10") (pinfunction "NC_10") (pintype "unspecified+no_connect"))
    )
    (net (code "78") (name "unconnected-(U4-RI-Pad1)") (class "Default")
      (node (ref "U4") (pin "1") (pinfunction "RI_1") (pintype "unspecified+no_connect"))
    )
    (net (code "79") (name "unconnected-(U4-SUSPEND#-Pad15)") (class "Default")
      (node (ref "U4") (pin "15") (pinfunction "SUSPEND#_15") (pintype "unspecified+no_connect"))
    )
    (net (code "80") (name "unconnected-(U4-SUSPEND-Pad17)") (class "Default")
      (node (ref "U4") (pin "17") (pinfunction "SUSPEND_17") (pintype "unspecified+no_connect"))
    )
    (net (code "81") (name "unconnected-(U4-VPP-Pad16)") (class "Default")
      (node (ref "U4") (pin "16") (pinfunction "VPP_16") (pintype "unspecified+no_connect"))
    )
    (net (code "82") (name "unconnected-(U7-INH-Pad8)") (class "Default")
      (node (ref "U7") (pin "8") (pinfunction "INH_8") (pintype "unspecified+no_connect"))
    )
    (net (code "83") (name "unconnected-(USB-C-SBU1-PadA8)") (class "Default")
      (node (ref "USB-C") (pin "A8") (pinfunction "SBU1_A8") (pintype "unspecified+no_connect"))
    )
    (net (code "84") (name "unconnected-(USB-C-SBU2-PadB8)") (class "Default")
      (node (ref "USB-C") (pin "B8") (pinfunction "SBU2_B8") (pintype "unspecified+no_connect"))
    )
  )
)
